# logica_de_arranque.net
KiCad netlist of a schematic drawn in Altium Designer
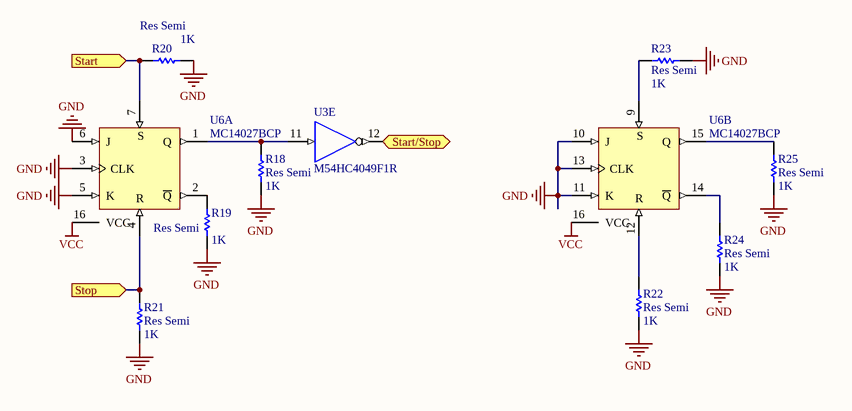
[diagram p0: logica de arranque.SchDoc]

(export (version "E")
  (design (tool "Eeschema 10.0.6"))
  (components
    (comp (ref "R18")
      (value "Res Semi")
      (footprint "2012[0805]")
      (description "Semiconductor Resistor")
      (fields (field (name "ALTIUM_VALUE") "1K") (field (name "PUBLISHER") "Altium Limited"))
      (libsource (lib "Miscellaneous Devices") (part "Res Semi"))
    )
    (comp (ref "R19")
      (value "Res Semi")
      (footprint "2012[0805]")
      (description "Semiconductor Resistor")
      (fields (field (name "ALTIUM_VALUE") "1K") (field (name "PUBLISHER") "Altium Limited"))
      (libsource (lib "Miscellaneous Devices") (part "Res Semi"))
    )
    (comp (ref "R20")
      (value "Res Semi")
      (footprint "2012[0805]")
      (description "Semiconductor Resistor")
      (fields (field (name "ALTIUM_VALUE") "1K") (field (name "PUBLISHER") "Altium Limited"))
      (libsource (lib "Miscellaneous Devices") (part "Res Semi"))
    )
    (comp (ref "R21")
      (value "Res Semi")
      (footprint "2012[0805]")
      (description "Semiconductor Resistor")
      (fields (field (name "ALTIUM_VALUE") "1K") (field (name "PUBLISHER") "Altium Limited"))
      (libsource (lib "Miscellaneous Devices") (part "Res Semi"))
    )
    (comp (ref "R22")
      (value "Res Semi")
      (footprint "2012[0805]")
      (description "Semiconductor Resistor")
      (fields (field (name "ALTIUM_VALUE") "1K") (field (name "PUBLISHER") "Altium Limited"))
      (libsource (lib "Miscellaneous Devices") (part "Res Semi"))
    )
    (comp (ref "R23")
      (value "Res Semi")
      (footprint "2012[0805]")
      (description "Semiconductor Resistor")
      (fields (field (name "ALTIUM_VALUE") "1K") (field (name "PUBLISHER") "Altium Limited"))
      (libsource (lib "Miscellaneous Devices") (part "Res Semi"))
    )
    (comp (ref "R24")
      (value "Res Semi")
      (footprint "2012[0805]")
      (description "Semiconductor Resistor")
      (fields (field (name "ALTIUM_VALUE") "1K") (field (name "PUBLISHER") "Altium Limited"))
      (libsource (lib "Miscellaneous Devices") (part "Res Semi"))
    )
    (comp (ref "R25")
      (value "Res Semi")
      (footprint "2012[0805]")
      (description "Semiconductor Resistor")
      (fields (field (name "ALTIUM_VALUE") "1K") (field (name "PUBLISHER") "Altium Limited"))
      (libsource (lib "Miscellaneous Devices") (part "Res Semi"))
    )
    (comp (ref "U3")
      (value "M54HC4049F1R")
      (footprint "DIP16")
      (description "Hex Buffer/Converter Invertering")
      (fields (field (name "PUBLISHER") "Altium Limited"))
      (libsource (lib "ST Logic Gate") (part "M54HC4049F1R"))
    )
    (comp (ref "U6")
      (value "MC14027BCP")
      (footprint "648-08")
      (description "Dual J-K Flip-Flop")
      (fields (field (name "PUBLISHER") "Altium Limited"))
      (libsource (lib "ON Semi Logic Flip-Flop") (part "MC14027BCP"))
    )
  )
  (nets
    (net (code "1") (name "/Start") (class "Default")
      (node (ref "R20") (pin "1") (pinfunction "1_1") (pintype "passive"))
      (node (ref "U6") (pin "7") (pinfunction "S_7") (pintype "input"))
    )
    (net (code "2") (name "/Start{slash}Stop") (class "Default")
      (node (ref "U3") (pin "12") (pinfunction "Y_12") (pintype "output"))
    )
    (net (code "3") (name "/Stop") (class "Default")
      (node (ref "R21") (pin "2") (pinfunction "2_2") (pintype "passive"))
      (node (ref "U6") (pin "4") (pinfunction "R_4") (pintype "input"))
    )
    (net (code "4") (name "GND") (class "Default")
      (node (ref "R18") (pin "2") (pinfunction "2_2") (pintype "passive"))
      (node (ref "R19") (pin "1") (pinfunction "1_1") (pintype "passive"))
      (node (ref "R20") (pin "2") (pinfunction "2_2") (pintype "passive"))
      (node (ref "R21") (pin "1") (pinfunction "1_1") (pintype "passive"))
      (node (ref "R22") (pin "1") (pinfunction "1_1") (pintype "passive"))
      (node (ref "R23") (pin "2") (pinfunction "2_2") (pintype "passive"))
      (node (ref "R24") (pin "1") (pinfunction "1_1") (pintype "passive"))
      (node (ref "R25") (pin "1") (pinfunction "1_1") (pintype "passive"))
      (node (ref "U3") (pin "8") (pinfunction "GND_8") (pintype "power_in"))
      (node (ref "U6") (pin "10") (pinfunction "J_10") (pintype "input"))
      (node (ref "U6") (pin "11") (pinfunction "K_11") (pintype "input"))
      (node (ref "U6") (pin "13") (pinfunction "CLK_13") (pintype "input"))
      (node (ref "U6") (pin "3") (pinfunction "CLK_3") (pintype "input"))
      (node (ref "U6") (pin "5") (pinfunction "K_5") (pintype "input"))
      (node (ref "U6") (pin "6") (pinfunction "J_6") (pintype "input"))
      (node (ref "U6") (pin "8") (pinfunction "GND_8") (pintype "power_in"))
    )
    (net (code "5") (name "Net-(U3E-A)") (class "Default")
      (node (ref "R18") (pin "1") (pinfunction "1_1") (pintype "passive"))
      (node (ref "U3") (pin "11") (pinfunction "A_11") (pintype "input"))
      (node (ref "U6") (pin "1") (pinfunction "Q_1") (pintype "output"))
    )
    (net (code "6") (name "Net-(U6A-~{Q})") (class "Default")
      (node (ref "R19") (pin "2") (pinfunction "2_2") (pintype "passive"))
      (node (ref "U6") (pin "2") (pinfunction "~{Q}_2") (pintype "output"))
    )
    (net (code "7") (name "Net-(U6B-Q)") (class "Default")
      (node (ref "R25") (pin "2") (pinfunction "2_2") (pintype "passive"))
      (node (ref "U6") (pin "15") (pinfunction "Q_15") (pintype "output"))
    )
    (net (code "8") (name "Net-(U6B-R)") (class "Default")
      (node (ref "R22") (pin "2") (pinfunction "2_2") (pintype "passive"))
      (node (ref "U6") (pin "12") (pinfunction "R_12") (pintype "input"))
    )
    (net (code "9") (name "Net-(U6B-S)") (class "Default")
      (node (ref "R23") (pin "1") (pinfunction "1_1") (pintype "passive"))
      (node (ref "U6") (pin "9") (pinfunction "S_9") (pintype "input"))
    )
    (net (code "10") (name "Net-(U6B-~{Q})") (class "Default")
      (node (ref "R24") (pin "2") (pinfunction "2_2") (pintype "passive"))
      (node (ref "U6") (pin "14") (pinfunction "~{Q}_14") (pintype "output"))
    )
    (net (code "11") (name "VCC") (class "Default")
      (node (ref "U3") (pin "1") (pinfunction "VCC_1") (pintype "power_in"))
      (node (ref "U6") (pin "16") (pinfunction "VCC_16") (pintype "power_in"))
    )
  )
)
